# Reserved_Sensor_Output_Socket.net
KiCad netlist of a schematic drawn in Altium Designer
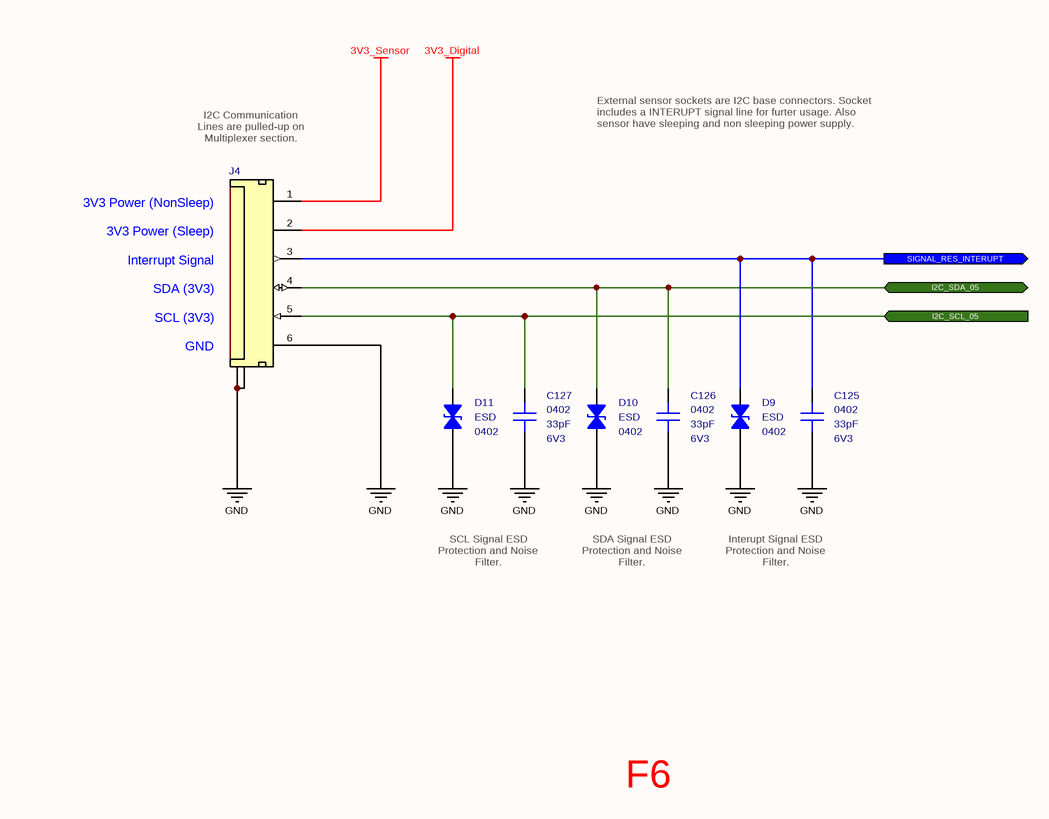
[diagram p0: Reserved Sensor Output Socket.SchDoc]

(export (version "E")
  (design (tool "Eeschema 10.0.6"))
  (components
    (comp (ref "C125")
      (value "33pF")
      (footprint "CAPACITOR_0402")
      (description "Capacitor - 33pF [0402] (Ceramic)")
      (fields
        (field (name "MANUFACTURER_PART_NUMBER") "C0402C330J9RACAUTO")
        (field (name "MOUSER_PART_NUMBER") "80-C0402C330J9RAUTO")
        (field (name "CASE") "0402")
        (field (name "VOLTAGE") "6V3")
      )
      (libsource (lib "Ovoo_Schematic") (part "Capacitor - 33pF [0402-6V3]"))
    )
    (comp (ref "C126")
      (value "33pF")
      (footprint "CAPACITOR_0402")
      (description "Capacitor - 33pF [0402] (Ceramic)")
      (fields
        (field (name "MANUFACTURER_PART_NUMBER") "C0402C330J9RACAUTO")
        (field (name "MOUSER_PART_NUMBER") "80-C0402C330J9RAUTO")
        (field (name "CASE") "0402")
        (field (name "VOLTAGE") "6V3")
      )
      (libsource (lib "Ovoo_Schematic") (part "Capacitor - 33pF [0402-6V3]"))
    )
    (comp (ref "C127")
      (value "33pF")
      (footprint "CAPACITOR_0402")
      (description "Capacitor - 33pF [0402] (Ceramic)")
      (fields
        (field (name "MANUFACTURER_PART_NUMBER") "C0402C330J9RACAUTO")
        (field (name "MOUSER_PART_NUMBER") "80-C0402C330J9RAUTO")
        (field (name "CASE") "0402")
        (field (name "VOLTAGE") "6V3")
      )
      (libsource (lib "Ovoo_Schematic") (part "Capacitor - 33pF [0402-6V3]"))
    )
    (comp (ref "D9")
      (value "ESD Suppressors")
      (footprint "ESD_0402")
      (description "TVS Diode (Bi-directional)")
      (fields
        (field (name "MANUFACTURER_PART_NUMBER") "0402ESDA-MLP1")
        (field (name "MOUSER_PART_NUMBER") "504-0402ESDA-MLP1")
        (field (name "CASE") "0402")
      )
      (libsource (lib "Ovoo_Schematic") (part "Diode - ESD Protection"))
    )
    (comp (ref "D10")
      (value "ESD Suppressors")
      (footprint "ESD_0402")
      (description "TVS Diode (Bi-directional)")
      (fields
        (field (name "MANUFACTURER_PART_NUMBER") "0402ESDA-MLP1")
        (field (name "MOUSER_PART_NUMBER") "504-0402ESDA-MLP1")
        (field (name "CASE") "0402")
      )
      (libsource (lib "Ovoo_Schematic") (part "Diode - ESD Protection"))
    )
    (comp (ref "D11")
      (value "ESD Suppressors")
      (footprint "ESD_0402")
      (description "TVS Diode (Bi-directional)")
      (fields
        (field (name "MANUFACTURER_PART_NUMBER") "0402ESDA-MLP1")
        (field (name "MOUSER_PART_NUMBER") "504-0402ESDA-MLP1")
        (field (name "CASE") "0402")
      )
      (libsource (lib "Ovoo_Schematic") (part "Diode - ESD Protection"))
    )
    (comp (ref "J4")
      (value "6P Tunic Connector")
      (footprint "Connector_Tunic 6P - H")
      (description "Mini Tunic Connector with 6P")
      (fields (field (name "MANUFACTURER_PART_NUMBER") "53261-0671"))
      (libsource (lib "Ovoo_Schematic") (part "Connector - Mini Tunic 6P (1.25)"))
    )
  )
  (nets
    (net (code "1") (name "/I2C_SCL_05") (class "Default")
      (node (ref "C127") (pin "2") (pinfunction "2_2") (pintype "passive"))
      (node (ref "D11") (pin "2") (pinfunction "2_2") (pintype "passive"))
      (node (ref "J4") (pin "5") (pinfunction "M_DRV_5") (pintype "input"))
    )
    (net (code "2") (name "/I2C_SDA_05") (class "Default")
      (node (ref "C126") (pin "2") (pinfunction "2_2") (pintype "passive"))
      (node (ref "D10") (pin "2") (pinfunction "2_2") (pintype "passive"))
      (node (ref "J4") (pin "4") (pinfunction "M_DRV_4") (pintype "bidirectional"))
    )
    (net (code "3") (name "/SIGNAL_RES_INTERUPT") (class "Default")
      (node (ref "C125") (pin "2") (pinfunction "2_2") (pintype "passive"))
      (node (ref "D9") (pin "2") (pinfunction "2_2") (pintype "passive"))
      (node (ref "J4") (pin "3") (pinfunction "M_DRV_3") (pintype "output"))
    )
    (net (code "4") (name "3V3_Digital") (class "Default")
      (node (ref "J4") (pin "2") (pinfunction "M_DRV_2") (pintype "passive"))
    )
    (net (code "5") (name "3V3_Sensor") (class "Default")
      (node (ref "J4") (pin "1") (pinfunction "VBAT_1") (pintype "passive"))
    )
    (net (code "6") (name "GND") (class "Default")
      (node (ref "C125") (pin "1") (pinfunction "1_1") (pintype "passive"))
      (node (ref "C126") (pin "1") (pinfunction "1_1") (pintype "passive"))
      (node (ref "C127") (pin "1") (pinfunction "1_1") (pintype "passive"))
      (node (ref "D10") (pin "1") (pinfunction "1_1") (pintype "passive"))
      (node (ref "D11") (pin "1") (pinfunction "1_1") (pintype "passive"))
      (node (ref "D9") (pin "1") (pinfunction "1_1") (pintype "passive"))
      (node (ref "J4") (pin "6") (pinfunction "M_DRV_6") (pintype "passive"))
      (node (ref "J4") (pin "7") (pinfunction "GND_7") (pintype "passive"))
      (node (ref "J4") (pin "8") (pinfunction "GND_8") (pintype "passive"))
    )
  )
)
